# Main.net
KiCad netlist of a schematic drawn in Altium Designer
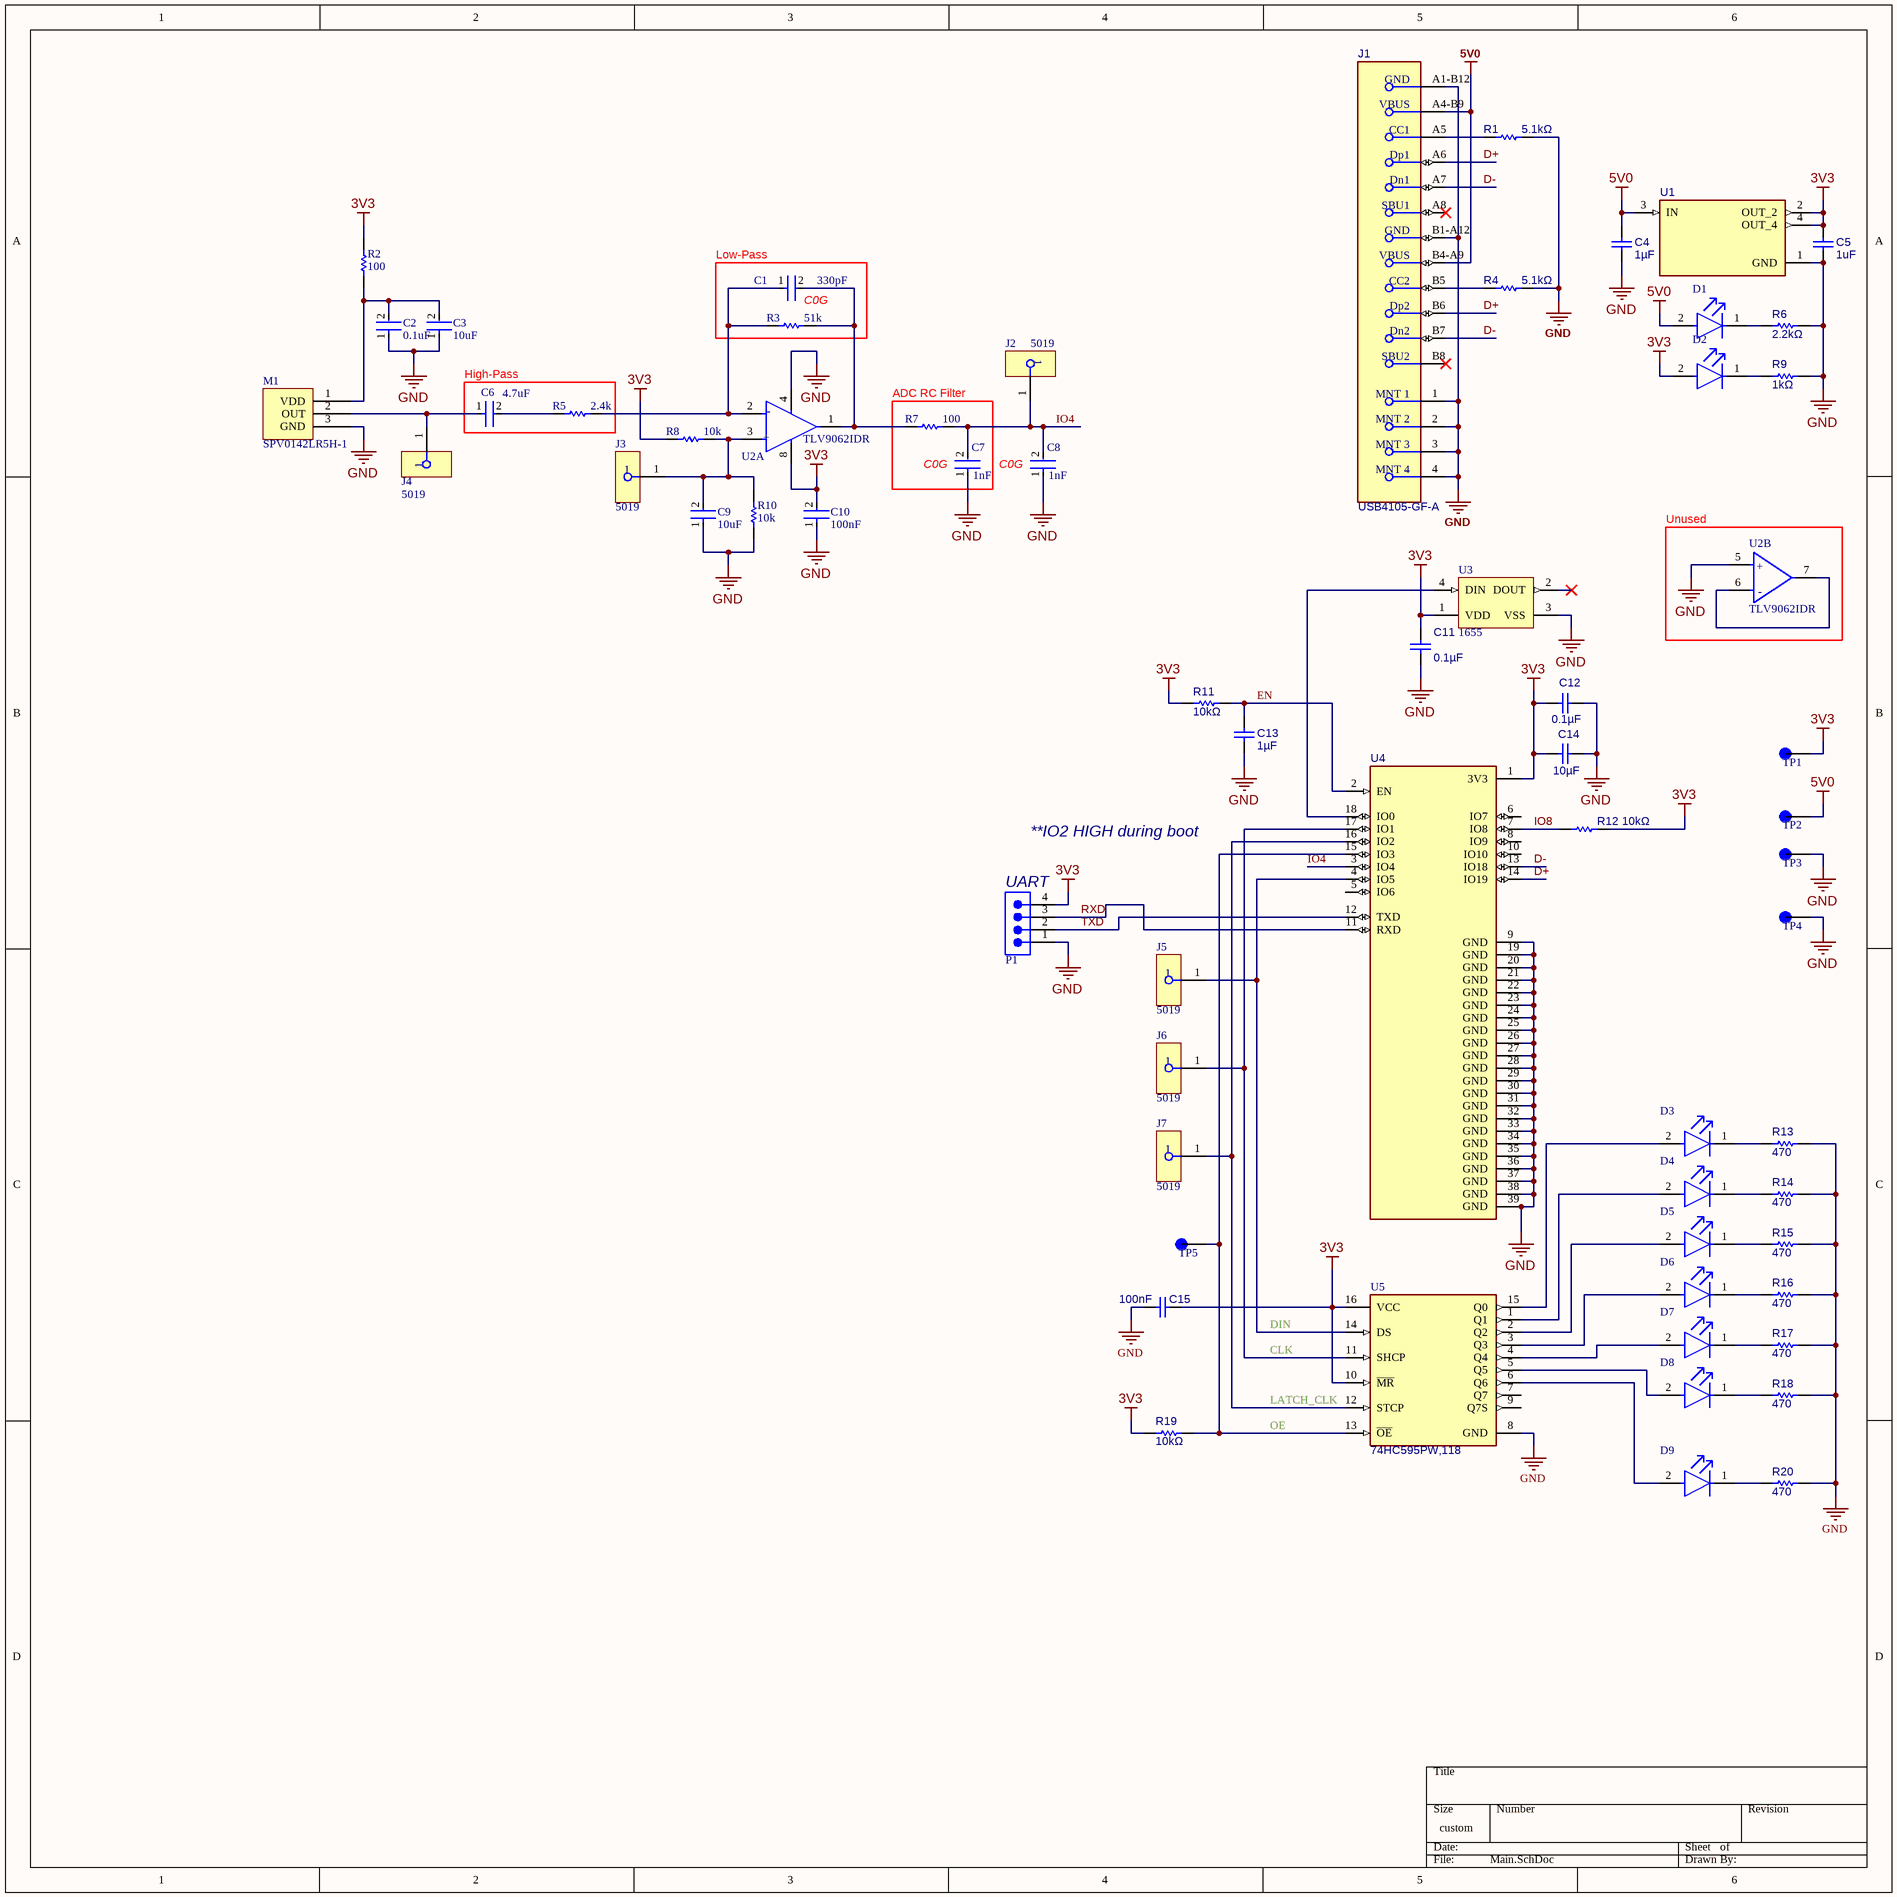
[diagram p0: Main.SchDoc]

(export (version "E")
  (design (tool "Eeschema 10.0.6"))
  (components
    (comp (ref "C1")
      (value "330pF")
      (footprint "FP-AC1206-0_85-IPC_C")
      (description "AC1206 22 nF X7R 10.00% 100 V")
      (fields
        (field (name "MANUFACTURER") "Yageo")
        (field (name "MANUFACTURER PART NUMBER") "AC1206KRX7R0BB223")
      )
      (libsource (lib "Altium Content Vault") (part "11868f565c42a9108669ba33697ecf6"))
    )
    (comp (ref "C2")
      (value "0.1uF")
      (footprint "FP-AC1206-0_85-IPC_C")
      (description "AC1206 22 nF X7R 10.00% 100 V")
      (fields
        (field (name "MANUFACTURER") "Yageo")
        (field (name "MANUFACTURER PART NUMBER") "AC1206KRX7R0BB223")
      )
      (libsource (lib "Altium Content Vault") (part "11868f565c42a9108669ba33697ecf6"))
    )
    (comp (ref "C3")
      (value "10uF")
      (footprint "FP-AC1206-0_85-IPC_C")
      (description "AC1206 22 nF X7R 10.00% 100 V")
      (fields
        (field (name "MANUFACTURER") "Yageo")
        (field (name "MANUFACTURER PART NUMBER") "AC1206KRX7R0BB223")
      )
      (libsource (lib "Altium Content Vault") (part "11868f565c42a9108669ba33697ecf6"))
    )
    (comp (ref "C4")
      (value "1µF")
      (footprint "WCAP-CSGP_0603_L1.6W0.8H0.8_Reflow")
      (description "10V tolerance")
      (libsource (lib "Altium Content Vault") (part "Capacitor_Non-Polarized"))
    )
    (comp (ref "C5")
      (value "1uF")
      (footprint "WCAP-CSGP_0603_L1.6W0.8H0.8_Reflow")
      (description "10V tolerance")
      (libsource (lib "Altium Content Vault") (part "Capacitor_Non-Polarized"))
    )
    (comp (ref "C6")
      (value "4.7uF")
      (footprint "FP-AC1206-0_85-IPC_C")
      (description "AC1206 22 nF X7R 10.00% 100 V")
      (fields
        (field (name "MANUFACTURER") "Yageo")
        (field (name "MANUFACTURER PART NUMBER") "AC1206KRX7R0BB223")
      )
      (libsource (lib "Altium Content Vault") (part "11868f565c42a9108669ba33697ecf6"))
    )
    (comp (ref "C7")
      (value "1nF")
      (footprint "FP-AC1206-0_85-IPC_C")
      (description "AC1206 22 nF X7R 10.00% 100 V")
      (fields
        (field (name "MANUFACTURER") "Yageo")
        (field (name "MANUFACTURER PART NUMBER") "AC1206KRX7R0BB223")
      )
      (libsource (lib "Altium Content Vault") (part "11868f565c42a9108669ba33697ecf6"))
    )
    (comp (ref "C8")
      (value "1nF")
      (footprint "FP-AC1206-0_85-IPC_C")
      (description "AC1206 22 nF X7R 10.00% 100 V")
      (fields
        (field (name "MANUFACTURER") "Yageo")
        (field (name "MANUFACTURER PART NUMBER") "AC1206KRX7R0BB223")
      )
      (libsource (lib "Altium Content Vault") (part "11868f565c42a9108669ba33697ecf6"))
    )
    (comp (ref "C9")
      (value "10uF")
      (footprint "FP-AC1206-0_85-IPC_C")
      (description "AC1206 22 nF X7R 10.00% 100 V")
      (fields
        (field (name "MANUFACTURER") "Yageo")
        (field (name "MANUFACTURER PART NUMBER") "AC1206KRX7R0BB223")
      )
      (libsource (lib "Altium Content Vault") (part "11868f565c42a9108669ba33697ecf6"))
    )
    (comp (ref "C10")
      (value "100nF")
      (footprint "FP-AC1206-0_85-IPC_C")
      (description "AC1206 22 nF X7R 10.00% 100 V")
      (fields
        (field (name "MANUFACTURER") "Yageo")
        (field (name "MANUFACTURER PART NUMBER") "AC1206KRX7R0BB223")
      )
      (libsource (lib "Altium Content Vault") (part "11868f565c42a9108669ba33697ecf6"))
    )
    (comp (ref "C11")
      (value "0.1µF")
      (footprint "WCAP-CSGP_0603_L1.6W0.8H0.8_Reflow")
      (description "10V tolerance")
      (libsource (lib "Altium Content Vault") (part "Capacitor_Non-Polarized"))
    )
    (comp (ref "C12")
      (value "0.1µF")
      (footprint "WCAP-CSGP_0603_L1.6W0.8H0.8_Reflow")
      (description "10V tolerance")
      (libsource (lib "Altium Content Vault") (part "Capacitor_Non-Polarized"))
    )
    (comp (ref "C13")
      (value "1µF")
      (footprint "WCAP-CSGP_0603_L1.6W0.8H0.8_Reflow")
      (description "10V tolerance")
      (libsource (lib "Altium Content Vault") (part "Capacitor_Non-Polarized"))
    )
    (comp (ref "C14")
      (value "10µF")
      (footprint "WCAP-CSGP_0603_L1.6W0.8H0.8_Reflow")
      (description "10V tolerance")
      (libsource (lib "Altium Content Vault") (part "Capacitor_Non-Polarized"))
    )
    (comp (ref "C15")
      (value "100nF")
      (footprint "WCAP-CSGP_0603_L1.6W0.8H0.8_Reflow")
      (description "10V tolerance")
      (libsource (lib "Altium Content Vault") (part "Capacitor_Non-Polarized"))
    )
    (comp (ref "D1")
      (value "LTST-C190KGKT")
      (footprint "FP-LTST-C190KGKT-MFG")
      (description "LED GREEN CLEAR CHIP SMD")
      (libsource (lib "Altium Content Vault") (part "8706943c75ba83719d021d2fdc84c58"))
    )
    (comp (ref "D2")
      (value "LTST-C190KGKT")
      (footprint "FP-LTST-C190KGKT-MFG")
      (description "LED GREEN CLEAR CHIP SMD")
      (libsource (lib "Altium Content Vault") (part "8706943c75ba83719d021d2fdc84c58"))
    )
    (comp (ref "D3")
      (value "LTST-C190KGKT")
      (footprint "FP-LTST-C190KGKT-MFG")
      (description "LED GREEN CLEAR CHIP SMD")
      (libsource (lib "Altium Content Vault") (part "8706943c75ba83719d021d2fdc84c58"))
    )
    (comp (ref "D4")
      (value "LTST-C190KGKT")
      (footprint "FP-LTST-C190KGKT-MFG")
      (description "LED GREEN CLEAR CHIP SMD")
      (libsource (lib "Altium Content Vault") (part "8706943c75ba83719d021d2fdc84c58"))
    )
    (comp (ref "D5")
      (value "LTST-C190KGKT")
      (footprint "FP-LTST-C190KGKT-MFG")
      (description "LED GREEN CLEAR CHIP SMD")
      (libsource (lib "Altium Content Vault") (part "8706943c75ba83719d021d2fdc84c58"))
    )
    (comp (ref "D6")
      (value "LTST-C190KGKT")
      (footprint "FP-LTST-C190KGKT-MFG")
      (description "LED GREEN CLEAR CHIP SMD")
      (libsource (lib "Altium Content Vault") (part "8706943c75ba83719d021d2fdc84c58"))
    )
    (comp (ref "D7")
      (value "LTST-C190KGKT")
      (footprint "FP-LTST-C190KGKT-MFG")
      (description "LED GREEN CLEAR CHIP SMD")
      (libsource (lib "Altium Content Vault") (part "8706943c75ba83719d021d2fdc84c58"))
    )
    (comp (ref "D8")
      (value "LTST-C190KGKT")
      (footprint "FP-LTST-C190KGKT-MFG")
      (description "LED GREEN CLEAR CHIP SMD")
      (libsource (lib "Altium Content Vault") (part "8706943c75ba83719d021d2fdc84c58"))
    )
    (comp (ref "D9")
      (value "LTST-C190KGKT")
      (footprint "FP-LTST-C190KGKT-MFG")
      (description "LED GREEN CLEAR CHIP SMD")
      (libsource (lib "Altium Content Vault") (part "8706943c75ba83719d021d2fdc84c58"))
    )
    (comp (ref "J1")
      (value "USB4105-GF-A")
      (footprint "FP-USB4105-GF-A-MFG")
      (description "CONN RCPT USB2.0 TYPEC 5A")
      (fields
        (field (name "MANUFACTURER") "GCT")
        (field (name "OCTOPART") "https://octopart.com/usb4105-gf-a-gct-106627878")
      )
      (libsource (lib "Altium Content Vault") (part "e7c17a616881a82b79941196b4bec10"))
    )
    (comp (ref "J2")
      (value "5019")
      (footprint "5019_MFG")
      (description "Phosphor Bronze Contact Miniature Silver Plated Surface Mount Test Points")
      (libsource (lib "") (part "2b5a64f1d553f7b761d27cd6d0c3a70_1"))
    )
    (comp (ref "J3")
      (value "5019")
      (footprint "5019_MFG")
      (description "Phosphor Bronze Contact Miniature Silver Plated Surface Mount Test Points")
      (libsource (lib "Altium Content Vault") (part "2b5a64f1d553f7b761d27cd6d0c3a70"))
    )
    (comp (ref "J4")
      (value "5019")
      (footprint "5019_MFG")
      (description "Phosphor Bronze Contact Miniature Silver Plated Surface Mount Test Points")
      (libsource (lib "") (part "2b5a64f1d553f7b761d27cd6d0c3a70_2"))
    )
    (comp (ref "J5")
      (value "5019")
      (footprint "5019_MFG")
      (description "Phosphor Bronze Contact Miniature Silver Plated Surface Mount Test Points")
      (libsource (lib "Altium Content Vault") (part "2b5a64f1d553f7b761d27cd6d0c3a70"))
    )
    (comp (ref "J6")
      (value "5019")
      (footprint "5019_MFG")
      (description "Phosphor Bronze Contact Miniature Silver Plated Surface Mount Test Points")
      (libsource (lib "Altium Content Vault") (part "2b5a64f1d553f7b761d27cd6d0c3a70"))
    )
    (comp (ref "J7")
      (value "5019")
      (footprint "5019_MFG")
      (description "Phosphor Bronze Contact Miniature Silver Plated Surface Mount Test Points")
      (libsource (lib "Altium Content Vault") (part "2b5a64f1d553f7b761d27cd6d0c3a70"))
    )
    (comp (ref "M1")
      (value "SPV0142LR5H-1")
      (footprint "SPV0142LR5H-1")
      (libsource (lib "SPV0142LR5H-1") (part "SPV0142LR5H-1"))
    )
    (comp (ref "P1")
      (value "61300411121")
      (footprint "61300411121")
      (description "THT Vertical Pin Header WR-PHD, Pitch 2.54 mm, Single Row, 4 pins")
      (libsource (lib "Altium Content Vault") (part "Header_Male_1R_04P"))
    )
    (comp (ref "R1")
      (value "5.1kΩ")
      (footprint "RESC1608X55X25NL10T15")
      (libsource (lib "Altium Content Vault") (part "RES"))
    )
    (comp (ref "R2")
      (value "100")
      (footprint "RESC3216X70X50NL05T20")
      (fields (field (name "PART NUMBER") "ERJ8ENF3300V") (field (name "MANUFACTURER") "Panasonic"))
      (libsource (lib "Altium Content Vault") (part "RES"))
    )
    (comp (ref "R3")
      (value "51k")
      (footprint "RESC3216X70X50NL05T20")
      (fields (field (name "PART NUMBER") "ERJ8ENF3300V") (field (name "MANUFACTURER") "Panasonic"))
      (libsource (lib "Altium Content Vault") (part "RES"))
    )
    (comp (ref "R4")
      (value "5.1kΩ")
      (footprint "RESC1608X55X25NL10T15")
      (libsource (lib "Altium Content Vault") (part "RES"))
    )
    (comp (ref "R5")
      (value "2.4k")
      (footprint "RESC3216X70X50NL05T20")
      (fields (field (name "PART NUMBER") "ERJ8ENF3300V") (field (name "MANUFACTURER") "Panasonic"))
      (libsource (lib "Altium Content Vault") (part "RES"))
    )
    (comp (ref "R6")
      (value "2.2kΩ")
      (footprint "RESC1608X55X25NL10T15")
      (libsource (lib "Altium Content Vault") (part "RES"))
    )
    (comp (ref "R7")
      (value "100")
      (footprint "RESC3216X70X50NL05T20")
      (fields (field (name "PART NUMBER") "ERJ8ENF3300V") (field (name "MANUFACTURER") "Panasonic"))
      (libsource (lib "Altium Content Vault") (part "RES"))
    )
    (comp (ref "R8")
      (value "10k")
      (footprint "RESC3216X70X50NL05T20")
      (fields (field (name "PART NUMBER") "ERJ8ENF3300V") (field (name "MANUFACTURER") "Panasonic"))
      (libsource (lib "Altium Content Vault") (part "RES"))
    )
    (comp (ref "R9")
      (value "1kΩ")
      (footprint "RESC1608X55X25NL10T15")
      (libsource (lib "Altium Content Vault") (part "RES"))
    )
    (comp (ref "R10")
      (value "10k")
      (footprint "RESC3216X70X50NL05T20")
      (fields (field (name "PART NUMBER") "ERJ8ENF3300V") (field (name "MANUFACTURER") "Panasonic"))
      (libsource (lib "Altium Content Vault") (part "RES"))
    )
    (comp (ref "R11")
      (value "10kΩ")
      (footprint "RESC1608X55X25NL10T15")
      (libsource (lib "Altium Content Vault") (part "RES"))
    )
    (comp (ref "R12")
      (value "10kΩ")
      (footprint "RESC1608X55X25NL10T15")
      (libsource (lib "Altium Content Vault") (part "RES"))
    )
    (comp (ref "R13")
      (value "470")
      (footprint "RESC1608X55X25NL10T15")
      (libsource (lib "Altium Content Vault") (part "RES"))
    )
    (comp (ref "R14")
      (value "470")
      (footprint "RESC1608X55X25NL10T15")
      (libsource (lib "Altium Content Vault") (part "RES"))
    )
    (comp (ref "R15")
      (value "470")
      (footprint "RESC1608X55X25NL10T15")
      (libsource (lib "Altium Content Vault") (part "RES"))
    )
    (comp (ref "R16")
      (value "470")
      (footprint "RESC1608X55X25NL10T15")
      (libsource (lib "Altium Content Vault") (part "RES"))
    )
    (comp (ref "R17")
      (value "470")
      (footprint "RESC1608X55X25NL10T15")
      (libsource (lib "Altium Content Vault") (part "RES"))
    )
    (comp (ref "R18")
      (value "470")
      (footprint "RESC1608X55X25NL10T15")
      (libsource (lib "Altium Content Vault") (part "RES"))
    )
    (comp (ref "R19")
      (value "10kΩ")
      (footprint "RESC1608X55X25NL10T15")
      (libsource (lib "Altium Content Vault") (part "RES"))
    )
    (comp (ref "R20")
      (value "470")
      (footprint "RESC1608X55X25NL10T15")
      (libsource (lib "Altium Content Vault") (part "RES"))
    )
    (comp (ref "TP1")
      (value "1035")
      (footprint "KEYSTONE_1035")
      (description "Test Point PC Slotted THM Height .335 Brass/Tin ¦ Keystone Electronics 1035")
      (fields (field (name "MF") "Keystone Electronics"))
      (libsource (lib "1035") (part "1035"))
    )
    (comp (ref "TP2")
      (value "1035")
      (footprint "KEYSTONE_1035")
      (description "Test Point PC Slotted THM Height .335 Brass/Tin ¦ Keystone Electronics 1035")
      (fields (field (name "MF") "Keystone Electronics"))
      (libsource (lib "1035") (part "1035"))
    )
    (comp (ref "TP3")
      (value "1035")
      (footprint "KEYSTONE_1035")
      (description "Test Point PC Slotted THM Height .335 Brass/Tin ¦ Keystone Electronics 1035")
      (fields (field (name "MF") "Keystone Electronics"))
      (libsource (lib "1035") (part "1035"))
    )
    (comp (ref "TP4")
      (value "1035")
      (footprint "KEYSTONE_1035")
      (description "Test Point PC Slotted THM Height .335 Brass/Tin ¦ Keystone Electronics 1035")
      (fields (field (name "MF") "Keystone Electronics"))
      (libsource (lib "1035") (part "1035"))
    )
    (comp (ref "TP5")
      (value "1035")
      (footprint "KEYSTONE_1035")
      (description "Test Point PC Slotted THM Height .335 Brass/Tin ¦ Keystone Electronics 1035")
      (fields (field (name "MF") "Keystone Electronics"))
      (libsource (lib "1035") (part "1035"))
    )
    (comp (ref "U1")
      (value "TLV1117LV33DCYR")
      (footprint "VREG_TLV1117LV33DCYR")
      (description "1-A, low-dropout voltage regulator")
      (fields (field (name "DIGI-KEY_PART_NUMBER") "296-28778-2-ND") (field (name "MF") "Texas Instruments"))
      (libsource (lib "TLV1117LV33DCYR") (part "TLV1117LV33DCYR"))
    )
    (comp (ref "U2")
      (value "TLV9062IDR")
      (footprint "FP-D0008A-MFG")
      (description "IC CMOS 2 CIRCUIT 8SOIC")
      (libsource (lib "Altium Content Vault") (part "d5b36c1049528187b1d2197d5d58d7e"))
    )
    (comp (ref "U3")
      (value "1655")
      (footprint "ADA-RGB-1655_V")
      (fields (field (name "MANUFACTURER") "Adafruit-Industries-LLC"))
      (libsource (lib "Altium Content Vault") (part "ADA-RGB-1655-4"))
    )
    (comp (ref "U4")
      (value "ESP32-C3-WROOM-02-N4")
      (footprint "MODULE_ESP32-C3-WROOM-02-H4")
      (fields (field (name "MF") "Espressif Systems"))
      (libsource (lib "ESP32-C3-WROOM-02-N4") (part "ESP32-C3-WROOM-02-N4"))
    )
    (comp (ref "U5")
      (value "74HC595PW,118")
      (footprint "FP-SOT403-1-MFG")
      (description "IC SHIFT REGISTER 8BIT 16TSSOP")
      (libsource (lib "Altium Content Vault") (part "27683e23285b137cd268a0f18c66bed"))
    )
  )
  (nets
    (net (code "1") (name "/CLK") (class "Default")
      (node (ref "J6") (pin "1") (pinfunction "1_1") (pintype "passive"))
      (node (ref "U4") (pin "17") (pinfunction "IO1_17") (pintype "bidirectional"))
      (node (ref "U5") (pin "11") (pinfunction "SHCP_11") (pintype "input"))
    )
    (net (code "2") (name "/D+") (class "Default")
      (node (ref "J1") (pin "A6") (pinfunction "Dp1_A6") (pintype "bidirectional"))
      (node (ref "J1") (pin "B6") (pinfunction "Dp2_B6") (pintype "bidirectional"))
      (node (ref "U4") (pin "14") (pinfunction "IO19_14") (pintype "bidirectional"))
    )
    (net (code "3") (name "/D-") (class "Default")
      (node (ref "J1") (pin "A7") (pinfunction "Dn1_A7") (pintype "bidirectional"))
      (node (ref "J1") (pin "B7") (pinfunction "Dn2_B7") (pintype "bidirectional"))
      (node (ref "U4") (pin "13") (pinfunction "IO18_13") (pintype "bidirectional"))
    )
    (net (code "4") (name "/DIN") (class "Default")
      (node (ref "J5") (pin "1") (pinfunction "1_1") (pintype "passive"))
      (node (ref "U4") (pin "4") (pinfunction "IO5_4") (pintype "bidirectional"))
      (node (ref "U5") (pin "14") (pinfunction "DS_14") (pintype "input"))
    )
    (net (code "5") (name "/EN") (class "Default")
      (node (ref "C13") (pin "2") (pinfunction "2_2") (pintype "passive"))
      (node (ref "R11") (pin "1") (pinfunction "1_1") (pintype "passive"))
      (node (ref "U4") (pin "2") (pinfunction "EN_2") (pintype "input"))
    )
    (net (code "6") (name "/IO4") (class "Default")
      (node (ref "C7") (pin "2") (pinfunction "2_2") (pintype "passive"))
      (node (ref "C8") (pin "2") (pinfunction "2_2") (pintype "passive"))
      (node (ref "J2") (pin "1") (pinfunction "1_1") (pintype "passive"))
      (node (ref "R7") (pin "2") (pinfunction "2_2") (pintype "passive"))
      (node (ref "U4") (pin "3") (pinfunction "IO4_3") (pintype "bidirectional"))
    )
    (net (code "7") (name "/IO8") (class "Default")
      (node (ref "R12") (pin "2") (pinfunction "2_2") (pintype "passive"))
      (node (ref "U4") (pin "7") (pinfunction "IO8_7") (pintype "bidirectional"))
    )
    (net (code "8") (name "/LATCH_CLK") (class "Default")
      (node (ref "J7") (pin "1") (pinfunction "1_1") (pintype "passive"))
      (node (ref "U4") (pin "16") (pinfunction "IO2_16") (pintype "bidirectional"))
      (node (ref "U5") (pin "12") (pinfunction "STCP_12") (pintype "input"))
    )
    (net (code "9") (name "/OE") (class "Default")
      (node (ref "R19") (pin "2") (pinfunction "2_2") (pintype "passive"))
      (node (ref "TP5") (pin "TP") (pinfunction "TP_TP") (pintype "passive"))
      (node (ref "U4") (pin "15") (pinfunction "IO3_15") (pintype "bidirectional"))
      (node (ref "U5") (pin "13") (pinfunction "~{OE}_13") (pintype "input"))
    )
    (net (code "10") (name "/RXD") (class "Default")
      (node (ref "P1") (pin "3") (pinfunction "3_3") (pintype "passive"))
      (node (ref "U4") (pin "11") (pinfunction "RXD_11") (pintype "bidirectional"))
    )
    (net (code "11") (name "/TXD") (class "Default")
      (node (ref "P1") (pin "2") (pinfunction "2_2") (pintype "passive"))
      (node (ref "U4") (pin "12") (pinfunction "TXD_12") (pintype "bidirectional"))
    )
    (net (code "12") (name "3V3") (class "Default")
      (node (ref "C10") (pin "2") (pinfunction "2_2") (pintype "passive"))
      (node (ref "C11") (pin "2") (pinfunction "2_2") (pintype "passive"))
      (node (ref "C12") (pin "1") (pinfunction "1_1") (pintype "passive"))
      (node (ref "C14") (pin "2") (pinfunction "2_2") (pintype "passive"))
      (node (ref "C15") (pin "2") (pinfunction "2_2") (pintype "passive"))
      (node (ref "C5") (pin "2") (pinfunction "2_2") (pintype "passive"))
      (node (ref "D2") (pin "2") (pinfunction "A_2") (pintype "passive"))
      (node (ref "P1") (pin "4") (pinfunction "4_4") (pintype "passive"))
      (node (ref "R11") (pin "2") (pinfunction "2_2") (pintype "passive"))
      (node (ref "R12") (pin "1") (pinfunction "1_1") (pintype "passive"))
      (node (ref "R19") (pin "1") (pinfunction "1_1") (pintype "passive"))
      (node (ref "R2") (pin "2") (pinfunction "2_2") (pintype "passive"))
      (node (ref "R8") (pin "1") (pinfunction "1_1") (pintype "passive"))
      (node (ref "TP1") (pin "TP") (pinfunction "TP_TP") (pintype "passive"))
      (node (ref "U1") (pin "2") (pinfunction "OUT_2_2") (pintype "output"))
      (node (ref "U1") (pin "4") (pinfunction "OUT_4_4") (pintype "output"))
      (node (ref "U2") (pin "8") (pinfunction "V+_8") (pintype "power_in"))
      (node (ref "U3") (pin "1") (pinfunction "VDD_1") (pintype "power_in"))
      (node (ref "U4") (pin "1") (pinfunction "3V3_1") (pintype "power_in"))
      (node (ref "U5") (pin "10") (pinfunction "~{MR}_10") (pintype "input"))
      (node (ref "U5") (pin "16") (pinfunction "VCC_16") (pintype "power_in"))
    )
    (net (code "13") (name "5V0") (class "Default")
      (node (ref "C4") (pin "2") (pinfunction "2_2") (pintype "passive"))
      (node (ref "D1") (pin "2") (pinfunction "A_2") (pintype "passive"))
      (node (ref "J1") (pin "A4-B9") (pinfunction "VBUS_A4-B9") (pintype "power_in"))
      (node (ref "J1") (pin "B4-A9") (pinfunction "VBUS_B4-A9") (pintype "bidirectional"))
      (node (ref "TP2") (pin "TP") (pinfunction "TP_TP") (pintype "passive"))
      (node (ref "U1") (pin "3") (pinfunction "IN_3") (pintype "input"))
    )
    (net (code "14") (name "GND") (class "Default")
      (node (ref "C10") (pin "1") (pinfunction "1_1") (pintype "passive"))
      (node (ref "C11") (pin "1") (pinfunction "1_1") (pintype "passive"))
      (node (ref "C12") (pin "2") (pinfunction "2_2") (pintype "passive"))
      (node (ref "C13") (pin "1") (pinfunction "1_1") (pintype "passive"))
      (node (ref "C14") (pin "1") (pinfunction "1_1") (pintype "passive"))
      (node (ref "C15") (pin "1") (pinfunction "1_1") (pintype "passive"))
      (node (ref "C2") (pin "1") (pinfunction "1_1") (pintype "passive"))
      (node (ref "C3") (pin "1") (pinfunction "1_1") (pintype "passive"))
      (node (ref "C4") (pin "1") (pinfunction "1_1") (pintype "passive"))
      (node (ref "C5") (pin "1") (pinfunction "1_1") (pintype "passive"))
      (node (ref "C7") (pin "1") (pinfunction "1_1") (pintype "passive"))
      (node (ref "C8") (pin "1") (pinfunction "1_1") (pintype "passive"))
      (node (ref "C9") (pin "1") (pinfunction "1_1") (pintype "passive"))
      (node (ref "J1") (pin "1") (pinfunction "MNT_1_1") (pintype "power_in"))
      (node (ref "J1") (pin "2") (pinfunction "MNT_2_2") (pintype "power_in"))
      (node (ref "J1") (pin "3") (pinfunction "MNT_3_3") (pintype "power_in"))
      (node (ref "J1") (pin "4") (pinfunction "MNT_4_4") (pintype "power_in"))
      (node (ref "J1") (pin "A1-B12") (pinfunction "GND_A1-B12") (pintype "power_in"))
      (node (ref "J1") (pin "B1-A12") (pinfunction "GND_B1-A12") (pintype "bidirectional"))
      (node (ref "M1") (pin "3") (pinfunction "GND_3") (pintype "passive"))
      (node (ref "P1") (pin "1") (pinfunction "1_1") (pintype "passive"))
      (node (ref "R1") (pin "1") (pinfunction "1_1") (pintype "passive"))
      (node (ref "R10") (pin "1") (pinfunction "1_1") (pintype "passive"))
      (node (ref "R13") (pin "1") (pinfunction "1_1") (pintype "passive"))
      (node (ref "R14") (pin "1") (pinfunction "1_1") (pintype "passive"))
      (node (ref "R15") (pin "1") (pinfunction "1_1") (pintype "passive"))
      (node (ref "R16") (pin "1") (pinfunction "1_1") (pintype "passive"))
      (node (ref "R17") (pin "1") (pinfunction "1_1") (pintype "passive"))
      (node (ref "R18") (pin "1") (pinfunction "1_1") (pintype "passive"))
      (node (ref "R20") (pin "1") (pinfunction "1_1") (pintype "passive"))
      (node (ref "R4") (pin "1") (pinfunction "1_1") (pintype "passive"))
      (node (ref "R6") (pin "1") (pinfunction "1_1") (pintype "passive"))
      (node (ref "R9") (pin "1") (pinfunction "1_1") (pintype "passive"))
      (node (ref "TP3") (pin "TP") (pinfunction "TP_TP") (pintype "passive"))
      (node (ref "TP4") (pin "TP") (pinfunction "TP_TP") (pintype "passive"))
      (node (ref "U1") (pin "1") (pinfunction "GND_1") (pintype "power_in"))
      (node (ref "U2") (pin "4") (pinfunction "V-_4") (pintype "power_in"))
      (node (ref "U2") (pin "5") (pinfunction "IN2+_5") (pintype "tri_state"))
      (node (ref "U3") (pin "3") (pinfunction "VSS_3") (pintype "power_in"))
      (node (ref "U4") (pin "19") (pinfunction "GND_19") (pintype "power_in"))
      (node (ref "U4") (pin "20") (pinfunction "GND_20") (pintype "power_in"))
      (node (ref "U4") (pin "21") (pinfunction "GND_21") (pintype "power_in"))
      (node (ref "U4") (pin "22") (pinfunction "GND_22") (pintype "power_in"))
      (node (ref "U4") (pin "23") (pinfunction "GND_23") (pintype "power_in"))
      (node (ref "U4") (pin "24") (pinfunction "GND_24") (pintype "power_in"))
      (node (ref "U4") (pin "25") (pinfunction "GND_25") (pintype "power_in"))
      (node (ref "U4") (pin "26") (pinfunction "GND_26") (pintype "power_in"))
      (node (ref "U4") (pin "27") (pinfunction "GND_27") (pintype "power_in"))
      (node (ref "U4") (pin "28") (pinfunction "GND_28") (pintype "power_in"))
      (node (ref "U4") (pin "29") (pinfunction "GND_29") (pintype "power_in"))
      (node (ref "U4") (pin "30") (pinfunction "GND_30") (pintype "power_in"))
      (node (ref "U4") (pin "31") (pinfunction "GND_31") (pintype "power_in"))
      (node (ref "U4") (pin "32") (pinfunction "GND_32") (pintype "power_in"))
      (node (ref "U4") (pin "33") (pinfunction "GND_33") (pintype "power_in"))
      (node (ref "U4") (pin "34") (pinfunction "GND_34") (pintype "power_in"))
      (node (ref "U4") (pin "35") (pinfunction "GND_35") (pintype "power_in"))
      (node (ref "U4") (pin "36") (pinfunction "GND_36") (pintype "power_in"))
      (node (ref "U4") (pin "37") (pinfunction "GND_37") (pintype "power_in"))
      (node (ref "U4") (pin "38") (pinfunction "GND_38") (pintype "power_in"))
      (node (ref "U4") (pin "39") (pinfunction "GND_39") (pintype "power_in"))
      (node (ref "U4") (pin "9") (pinfunction "GND_9") (pintype "power_in"))
      (node (ref "U5") (pin "8") (pinfunction "GND_8") (pintype "power_in"))
    )
    (net (code "15") (name "Net-(C6-Pad2)") (class "Default")
      (node (ref "C6") (pin "2") (pinfunction "2_2") (pintype "passive"))
      (node (ref "R5") (pin "1") (pinfunction "1_1") (pintype "passive"))
    )
    (net (code "16") (name "Net-(D1-C)") (class "Default")
      (node (ref "D1") (pin "1") (pinfunction "C_1") (pintype "passive"))
      (node (ref "R6") (pin "2") (pinfunction "2_2") (pintype "passive"))
    )
    (net (code "17") (name "Net-(D2-C)") (class "Default")
      (node (ref "D2") (pin "1") (pinfunction "C_1") (pintype "passive"))
      (node (ref "R9") (pin "2") (pinfunction "2_2") (pintype "passive"))
    )
    (net (code "18") (name "Net-(D3-A)") (class "Default")
      (node (ref "D3") (pin "2") (pinfunction "A_2") (pintype "passive"))
      (node (ref "U5") (pin "15") (pinfunction "Q0_15") (pintype "output"))
    )
    (net (code "19") (name "Net-(D3-C)") (class "Default")
      (node (ref "D3") (pin "1") (pinfunction "C_1") (pintype "passive"))
      (node (ref "R13") (pin "2") (pinfunction "2_2") (pintype "passive"))
    )
    (net (code "20") (name "Net-(D4-A)") (class "Default")
      (node (ref "D4") (pin "2") (pinfunction "A_2") (pintype "passive"))
      (node (ref "U5") (pin "1") (pinfunction "Q1_1") (pintype "output"))
    )
    (net (code "21") (name "Net-(D4-C)") (class "Default")
      (node (ref "D4") (pin "1") (pinfunction "C_1") (pintype "passive"))
      (node (ref "R14") (pin "2") (pinfunction "2_2") (pintype "passive"))
    )
    (net (code "22") (name "Net-(D5-A)") (class "Default")
      (node (ref "D5") (pin "2") (pinfunction "A_2") (pintype "passive"))
      (node (ref "U5") (pin "2") (pinfunction "Q2_2") (pintype "output"))
    )
    (net (code "23") (name "Net-(D5-C)") (class "Default")
      (node (ref "D5") (pin "1") (pinfunction "C_1") (pintype "passive"))
      (node (ref "R15") (pin "2") (pinfunction "2_2") (pintype "passive"))
    )
    (net (code "24") (name "Net-(D6-A)") (class "Default")
      (node (ref "D6") (pin "2") (pinfunction "A_2") (pintype "passive"))
      (node (ref "U5") (pin "3") (pinfunction "Q3_3") (pintype "output"))
    )
    (net (code "25") (name "Net-(D6-C)") (class "Default")
      (node (ref "D6") (pin "1") (pinfunction "C_1") (pintype "passive"))
      (node (ref "R16") (pin "2") (pinfunction "2_2") (pintype "passive"))
    )
    (net (code "26") (name "Net-(D7-A)") (class "Default")
      (node (ref "D7") (pin "2") (pinfunction "A_2") (pintype "passive"))
      (node (ref "U5") (pin "4") (pinfunction "Q4_4") (pintype "output"))
    )
    (net (code "27") (name "Net-(D7-C)") (class "Default")
      (node (ref "D7") (pin "1") (pinfunction "C_1") (pintype "passive"))
      (node (ref "R17") (pin "2") (pinfunction "2_2") (pintype "passive"))
    )
    (net (code "28") (name "Net-(D8-A)") (class "Default")
      (node (ref "D8") (pin "2") (pinfunction "A_2") (pintype "passive"))
      (node (ref "U5") (pin "5") (pinfunction "Q5_5") (pintype "output"))
    )
    (net (code "29") (name "Net-(D8-C)") (class "Default")
      (node (ref "D8") (pin "1") (pinfunction "C_1") (pintype "passive"))
      (node (ref "R18") (pin "2") (pinfunction "2_2") (pintype "passive"))
    )
    (net (code "30") (name "Net-(D9-A)") (class "Default")
      (node (ref "D9") (pin "2") (pinfunction "A_2") (pintype "passive"))
      (node (ref "U5") (pin "6") (pinfunction "Q6_6") (pintype "output"))
    )
    (net (code "31") (name "Net-(D9-C)") (class "Default")
      (node (ref "D9") (pin "1") (pinfunction "C_1") (pintype "passive"))
      (node (ref "R20") (pin "2") (pinfunction "2_2") (pintype "passive"))
    )
    (net (code "32") (name "Net-(J1-CC1)") (class "Default")
      (node (ref "J1") (pin "A5") (pinfunction "CC1_A5") (pintype "power_in"))
      (node (ref "R1") (pin "2") (pinfunction "2_2") (pintype "passive"))
    )
    (net (code "33") (name "Net-(J1-CC2)") (class "Default")
      (node (ref "J1") (pin "B5") (pinfunction "CC2_B5") (pintype "bidirectional"))
      (node (ref "R4") (pin "2") (pinfunction "2_2") (pintype "passive"))
    )
    (net (code "34") (name "Net-(M1-OUT)") (class "Default")
      (node (ref "C6") (pin "1") (pinfunction "1_1") (pintype "passive"))
      (node (ref "J4") (pin "1") (pinfunction "1_1") (pintype "passive"))
      (node (ref "M1") (pin "2") (pinfunction "OUT_2") (pintype "passive"))
    )
    (net (code "35") (name "Net-(M1-VDD)") (class "Default")
      (node (ref "C2") (pin "2") (pinfunction "2_2") (pintype "passive"))
      (node (ref "C3") (pin "2") (pinfunction "2_2") (pintype "passive"))
      (node (ref "M1") (pin "1") (pinfunction "VDD_1") (pintype "passive"))
      (node (ref "R2") (pin "1") (pinfunction "1_1") (pintype "passive"))
    )
    (net (code "36") (name "Net-(U2A-IN1+)") (class "Default")
      (node (ref "C9") (pin "2") (pinfunction "2_2") (pintype "passive"))
      (node (ref "J3") (pin "1") (pinfunction "1_1") (pintype "passive"))
      (node (ref "R10") (pin "2") (pinfunction "2_2") (pintype "passive"))
      (node (ref "R8") (pin "2") (pinfunction "2_2") (pintype "passive"))
      (node (ref "U2") (pin "3") (pinfunction "IN1+_3") (pintype "tri_state"))
    )
    (net (code "37") (name "Net-(U2A-IN1-)") (class "Default")
      (node (ref "C1") (pin "1") (pinfunction "1_1") (pintype "passive"))
      (node (ref "R3") (pin "1") (pinfunction "1_1") (pintype "passive"))
      (node (ref "R5") (pin "2") (pinfunction "2_2") (pintype "passive"))
      (node (ref "U2") (pin "2") (pinfunction "IN1-_2") (pintype "tri_state"))
    )
    (net (code "38") (name "Net-(U2A-OUT1)") (class "Default")
      (node (ref "C1") (pin "2") (pinfunction "2_2") (pintype "passive"))
      (node (ref "R3") (pin "2") (pinfunction "2_2") (pintype "passive"))
      (node (ref "R7") (pin "1") (pinfunction "1_1") (pintype "passive"))
      (node (ref "U2") (pin "1") (pinfunction "OUT1_1") (pintype "passive"))
    )
    (net (code "39") (name "Net-(U2B-IN2-)") (class "Default")
      (node (ref "U2") (pin "6") (pinfunction "IN2-_6") (pintype "tri_state"))
      (node (ref "U2") (pin "7") (pinfunction "OUT2_7") (pintype "passive"))
    )
    (net (code "40") (name "Net-(U3-DIN)") (class "Default")
      (node (ref "U3") (pin "4") (pinfunction "DIN_4") (pintype "input"))
      (node (ref "U4") (pin "18") (pinfunction "IO0_18") (pintype "bidirectional"))
    )
    (net (code "41") (name "unconnected-(J1-SBU1-PadA8)") (class "Default")
      (node (ref "J1") (pin "A8") (pinfunction "SBU1_A8") (pintype "bidirectional+no_connect"))
    )
    (net (code "42") (name "unconnected-(J1-SBU2-PadB8)") (class "Default")
      (node (ref "J1") (pin "B8") (pinfunction "SBU2_B8") (pintype "power_in+no_connect"))
    )
    (net (code "43") (name "unconnected-(U3-DOUT-Pad2)") (class "Default")
      (node (ref "U3") (pin "2") (pinfunction "DOUT_2") (pintype "output+no_connect"))
    )
    (net (code "44") (name "unconnected-(U4-IO6-Pad5)") (class "Default")
      (node (ref "U4") (pin "5") (pinfunction "IO6_5") (pintype "bidirectional"))
    )
    (net (code "45") (name "unconnected-(U4-IO7-Pad6)") (class "Default")
      (node (ref "U4") (pin "6") (pinfunction "IO7_6") (pintype "bidirectional"))
    )
    (net (code "46") (name "unconnected-(U4-IO9-Pad8)") (class "Default")
      (node (ref "U4") (pin "8") (pinfunction "IO9_8") (pintype "bidirectional"))
    )
    (net (code "47") (name "unconnected-(U4-IO10-Pad10)") (class "Default")
      (node (ref "U4") (pin "10") (pinfunction "IO10_10") (pintype "bidirectional"))
    )
    (net (code "48") (name "unconnected-(U5-Q7-Pad7)") (class "Default")
      (node (ref "U5") (pin "7") (pinfunction "Q7_7") (pintype "output"))
    )
    (net (code "49") (name "unconnected-(U5-Q7S-Pad9)") (class "Default")
      (node (ref "U5") (pin "9") (pinfunction "Q7S_9") (pintype "output"))
    )
  )
)
